# LPC-LINK-2_SHIELD.net
KiCad netlist of a schematic drawn in Altium Designer
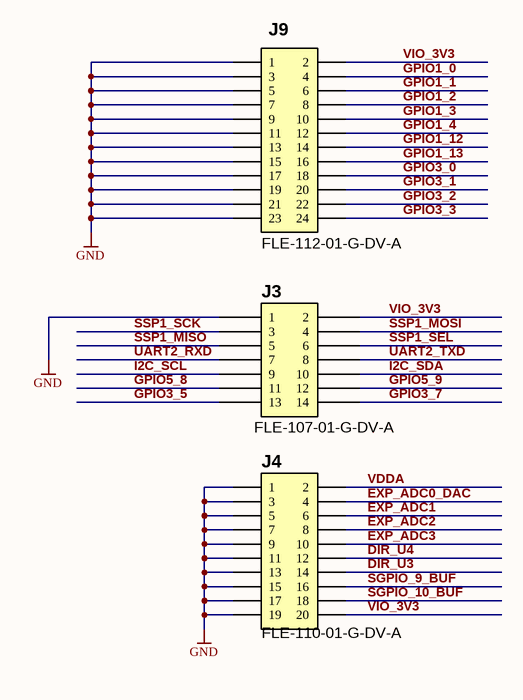
[diagram p0: LPC-LINK-2_SHIELD.SchDoc]

(export (version "E")
  (design (tool "Eeschema 10.0.6"))
  (components
    (comp (ref "J3")
      (value "FLE-107-01-G-DV-A")
      (footprint "FLE-107-01-G-DV-A")
      (description "SAMTEC - FLE-107-01-G-DV-A - .050 MICRO STRIPS")
      (fields (field (name "MANUFACTURER") "SAMTEC"))
      (libsource (lib "eConnector") (part "FLE-107-01-G-DV-A"))
    )
    (comp (ref "J4")
      (value "FLE-110-01-G-DV-A")
      (footprint "FLE-110-01-G-DV-A")
      (description "SAMTEC - FLE-110-01-G-DV-A - .050 MICRO STRIPS")
      (fields (field (name "MANUFACTURER") "SAMTEC"))
      (libsource (lib "eConnector") (part "FLE-110-01-G-DV-A"))
    )
    (comp (ref "J9")
      (value "FLE-112-01-G-DV-A")
      (footprint "FLE-112-01-G-DV-A")
      (description "SAMTEC - FLE-112-01-G-DV-A - .050 MICRO STRIPS")
      (fields (field (name "MANUFACTURER") "SAMTEC"))
      (libsource (lib "eConnector") (part "FLE-112-01-G-DV-A"))
    )
  )
  (nets
    (net (code "1") (name "/DIR_U3") (class "Default")
      (node (ref "J4") (pin "14") (pinfunction "14_14") (pintype "passive"))
    )
    (net (code "2") (name "/DIR_U4") (class "Default")
      (node (ref "J4") (pin "12") (pinfunction "12_12") (pintype "passive"))
    )
    (net (code "3") (name "/EXP_ADC0_DAC") (class "Default")
      (node (ref "J4") (pin "4") (pinfunction "4_4") (pintype "passive"))
    )
    (net (code "4") (name "/EXP_ADC1") (class "Default")
      (node (ref "J4") (pin "6") (pinfunction "6_6") (pintype "passive"))
    )
    (net (code "5") (name "/EXP_ADC2") (class "Default")
      (node (ref "J4") (pin "8") (pinfunction "8_8") (pintype "passive"))
    )
    (net (code "6") (name "/EXP_ADC3") (class "Default")
      (node (ref "J4") (pin "10") (pinfunction "10_10") (pintype "passive"))
    )
    (net (code "7") (name "/GPIO1_0") (class "Default")
      (node (ref "J9") (pin "4") (pinfunction "4_4") (pintype "passive"))
    )
    (net (code "8") (name "/GPIO1_1") (class "Default")
      (node (ref "J9") (pin "6") (pinfunction "6_6") (pintype "passive"))
    )
    (net (code "9") (name "/GPIO1_2") (class "Default")
      (node (ref "J9") (pin "8") (pinfunction "8_8") (pintype "passive"))
    )
    (net (code "10") (name "/GPIO1_3") (class "Default")
      (node (ref "J9") (pin "10") (pinfunction "10_10") (pintype "passive"))
    )
    (net (code "11") (name "/GPIO1_4") (class "Default")
      (node (ref "J9") (pin "12") (pinfunction "12_12") (pintype "passive"))
    )
    (net (code "12") (name "/GPIO1_12") (class "Default")
      (node (ref "J9") (pin "14") (pinfunction "14_14") (pintype "passive"))
    )
    (net (code "13") (name "/GPIO1_13") (class "Default")
      (node (ref "J9") (pin "16") (pinfunction "16_16") (pintype "passive"))
    )
    (net (code "14") (name "/GPIO3_0") (class "Default")
      (node (ref "J9") (pin "18") (pinfunction "18_18") (pintype "passive"))
    )
    (net (code "15") (name "/GPIO3_1") (class "Default")
      (node (ref "J9") (pin "20") (pinfunction "20_20") (pintype "passive"))
    )
    (net (code "16") (name "/GPIO3_2") (class "Default")
      (node (ref "J9") (pin "22") (pinfunction "22_22") (pintype "passive"))
    )
    (net (code "17") (name "/GPIO3_3") (class "Default")
      (node (ref "J9") (pin "24") (pinfunction "24_24") (pintype "passive"))
    )
    (net (code "18") (name "/GPIO3_5") (class "Default")
      (node (ref "J3") (pin "13") (pinfunction "13_13") (pintype "passive"))
    )
    (net (code "19") (name "/GPIO3_7") (class "Default")
      (node (ref "J3") (pin "14") (pinfunction "14_14") (pintype "passive"))
    )
    (net (code "20") (name "/GPIO5_8") (class "Default")
      (node (ref "J3") (pin "11") (pinfunction "11_11") (pintype "passive"))
    )
    (net (code "21") (name "/GPIO5_9") (class "Default")
      (node (ref "J3") (pin "12") (pinfunction "12_12") (pintype "passive"))
    )
    (net (code "22") (name "/I2C_SCL") (class "Default")
      (node (ref "J3") (pin "9") (pinfunction "9_9") (pintype "passive"))
    )
    (net (code "23") (name "/I2C_SDA") (class "Default")
      (node (ref "J3") (pin "10") (pinfunction "10_10") (pintype "passive"))
    )
    (net (code "24") (name "/SGPIO_9_BUF") (class "Default")
      (node (ref "J4") (pin "16") (pinfunction "16_16") (pintype "passive"))
    )
    (net (code "25") (name "/SGPIO_10_BUF") (class "Default")
      (node (ref "J4") (pin "18") (pinfunction "18_18") (pintype "passive"))
    )
    (net (code "26") (name "/SSP1_MISO") (class "Default")
      (node (ref "J3") (pin "5") (pinfunction "5_5") (pintype "passive"))
    )
    (net (code "27") (name "/SSP1_MOSI") (class "Default")
      (node (ref "J3") (pin "4") (pinfunction "4_4") (pintype "passive"))
    )
    (net (code "28") (name "/SSP1_SCK") (class "Default")
      (node (ref "J3") (pin "3") (pinfunction "3_3") (pintype "passive"))
    )
    (net (code "29") (name "/SSP1_SEL") (class "Default")
      (node (ref "J3") (pin "6") (pinfunction "6_6") (pintype "passive"))
    )
    (net (code "30") (name "/UART2_RXD") (class "Default")
      (node (ref "J3") (pin "7") (pinfunction "7_7") (pintype "passive"))
    )
    (net (code "31") (name "/UART2_TXD") (class "Default")
      (node (ref "J3") (pin "8") (pinfunction "8_8") (pintype "passive"))
    )
    (net (code "32") (name "/VDDA") (class "Default")
      (node (ref "J4") (pin "2") (pinfunction "2_2") (pintype "passive"))
    )
    (net (code "33") (name "/VIO_3V3") (class "Default")
      (node (ref "J3") (pin "2") (pinfunction "2_2") (pintype "passive"))
      (node (ref "J4") (pin "20") (pinfunction "20_20") (pintype "passive"))
      (node (ref "J9") (pin "2") (pinfunction "2_2") (pintype "passive"))
    )
    (net (code "34") (name "GND") (class "Default")
      (node (ref "J3") (pin "1") (pinfunction "1_1") (pintype "passive"))
      (node (ref "J4") (pin "1") (pinfunction "1_1") (pintype "passive"))
      (node (ref "J4") (pin "11") (pinfunction "11_11") (pintype "passive"))
      (node (ref "J4") (pin "13") (pinfunction "13_13") (pintype "passive"))
      (node (ref "J4") (pin "15") (pinfunction "15_15") (pintype "passive"))
      (node (ref "J4") (pin "17") (pinfunction "17_17") (pintype "passive"))
      (node (ref "J4") (pin "19") (pinfunction "19_19") (pintype "passive"))
      (node (ref "J4") (pin "3") (pinfunction "3_3") (pintype "passive"))
      (node (ref "J4") (pin "5") (pinfunction "5_5") (pintype "passive"))
      (node (ref "J4") (pin "7") (pinfunction "7_7") (pintype "passive"))
      (node (ref "J4") (pin "9") (pinfunction "9_9") (pintype "passive"))
      (node (ref "J9") (pin "1") (pinfunction "1_1") (pintype "passive"))
      (node (ref "J9") (pin "11") (pinfunction "11_11") (pintype "passive"))
      (node (ref "J9") (pin "13") (pinfunction "13_13") (pintype "passive"))
      (node (ref "J9") (pin "15") (pinfunction "15_15") (pintype "passive"))
      (node (ref "J9") (pin "17") (pinfunction "17_17") (pintype "passive"))
      (node (ref "J9") (pin "19") (pinfunction "19_19") (pintype "passive"))
      (node (ref "J9") (pin "21") (pinfunction "21_21") (pintype "passive"))
      (node (ref "J9") (pin "23") (pinfunction "23_23") (pintype "passive"))
      (node (ref "J9") (pin "3") (pinfunction "3_3") (pintype "passive"))
      (node (ref "J9") (pin "5") (pinfunction "5_5") (pintype "passive"))
      (node (ref "J9") (pin "7") (pinfunction "7_7") (pintype "passive"))
      (node (ref "J9") (pin "9") (pinfunction "9_9") (pintype "passive"))
    )
  )
)
